# VoltageRegulators.net
KiCad netlist of a schematic drawn in Altium Designer
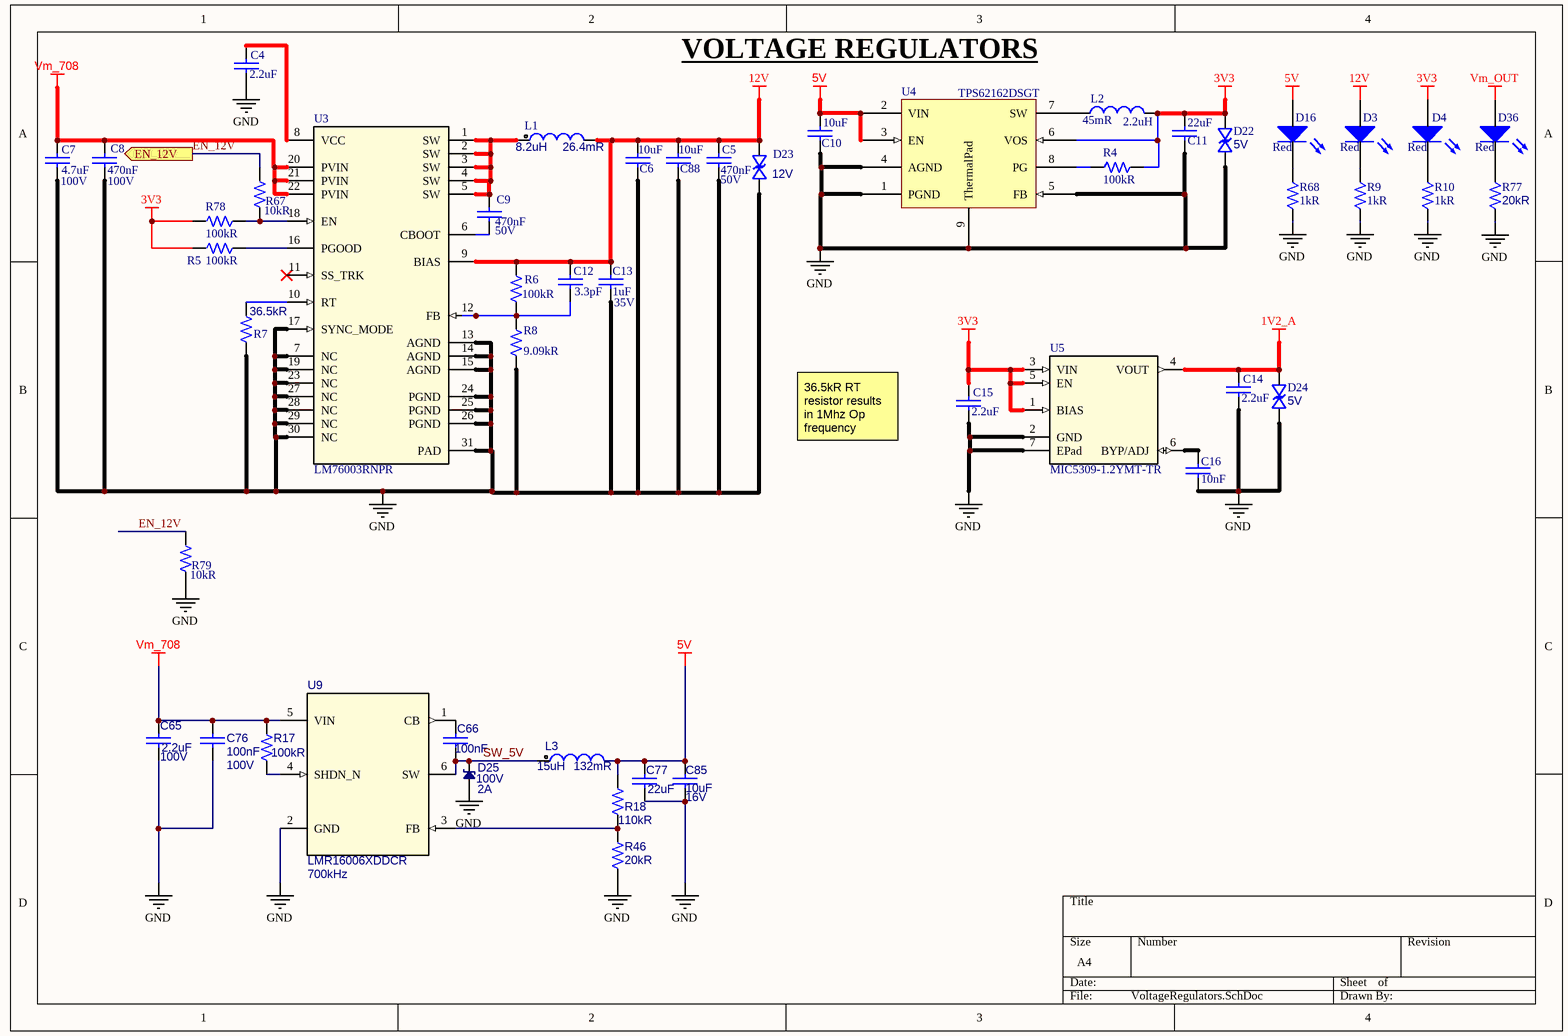
[diagram p0: VoltageRegulators.SchDoc]

(export (version "E")
  (design (tool "Eeschema 10.0.6"))
  (components
    (comp (ref "C4")
      (value "Capacitor")
      (footprint "CAP0402")
      (fields (field (name "CAPACITANCE") "2.2uF"))
      (libsource (lib "BPL-ShematicLibrary") (part "Capacitor"))
    )
    (comp (ref "C5")
      (value "Capacitor")
      (footprint "CAP0603")
      (fields (field (name "CAPACITANCE") "470nF") (field (name "VOLTAGE RATING") "50V"))
      (libsource (lib "") (part "Capacitor_1"))
    )
    (comp (ref "C6")
      (value "10uF")
      (footprint "CAP0603")
      (description "Capacitor")
      (fields
        (field (name "MANUFACTURER") "Murata")
        (field (name "MANUFACTURER PART NUMBER") "GRM188R61E106MA73J")
      )
      (libsource (lib "") (part "Capacitor_1"))
    )
    (comp (ref "C7")
      (value "Capacitor")
      (footprint "CAP1210")
      (fields
        (field (name "CAPACITANCE") "4.7uF")
        (field (name "VOLTAGE RATING") "100V")
        (field (name "TOLERANCE") "10%")
      )
      (libsource (lib "") (part "Capacitor_1"))
    )
    (comp (ref "C8")
      (value "Capacitor")
      (footprint "CAP0805")
      (fields (field (name "CAPACITANCE") "470nF") (field (name "VOLTAGE RATING") "100V"))
      (libsource (lib "") (part "Capacitor_1"))
    )
    (comp (ref "C9")
      (value "Capacitor")
      (footprint "CAP0603")
      (fields (field (name "CAPACITANCE") "470nF") (field (name "VOLTAGE RATING") "50V"))
      (libsource (lib "") (part "Capacitor_1"))
    )
    (comp (ref "C10")
      (value "10uF")
      (footprint "CAP0603")
      (description "Capacitor")
      (fields
        (field (name "MANUFACTURER") "Murata")
        (field (name "MANUFACTURER PART NUMBER") "GRM188R61E106MA73J")
      )
      (libsource (lib "") (part "Capacitor_1"))
    )
    (comp (ref "C11")
      (value "22uF")
      (footprint "CAP0603")
      (description "Capacitor")
      (fields
        (field (name "MANUFACTURER") "Samsung")
        (field (name "MANUFACTURER PART NUMBER") "CL10A226MO7JZNC")
      )
      (libsource (lib "") (part "Capacitor_1"))
    )
    (comp (ref "C12")
      (value "Capacitor")
      (footprint "CAP0402")
      (fields (field (name "CAPACITANCE") "3.3pF"))
      (libsource (lib "BPL-ShematicLibrary") (part "Capacitor"))
    )
    (comp (ref "C13")
      (value "Capacitor")
      (footprint "CAP0402")
      (fields (field (name "VOLTAGE RATING") "35V") (field (name "CAPACITANCE") "1uF"))
      (libsource (lib "") (part "Capacitor_1"))
    )
    (comp (ref "C14")
      (value "Capacitor")
      (footprint "CAP0402")
      (fields (field (name "CAPACITANCE") "2.2uF"))
      (libsource (lib "BPL-ShematicLibrary") (part "Capacitor"))
    )
    (comp (ref "C15")
      (value "Capacitor")
      (footprint "CAP0402")
      (fields (field (name "CAPACITANCE") "2.2uF"))
      (libsource (lib "BPL-ShematicLibrary") (part "Capacitor"))
    )
    (comp (ref "C16")
      (value "Capacitor")
      (footprint "CAP0402")
      (fields (field (name "CAPACITANCE") "10nF"))
      (libsource (lib "BPL-ShematicLibrary") (part "Capacitor"))
    )
    (comp (ref "C65")
      (value "Capacitor")
      (footprint "CAP1206")
      (description "CAP CER 2.2UF 100V X7R 1206")
      (fields (field (name "CAPACITANCE") "2.2uF") (field (name "VOLTAGE RATING") "100V"))
      (libsource (lib "BPL-ShematicLibrary") (part "Capacitor"))
    )
    (comp (ref "C66")
      (value "Capacitor")
      (footprint "CAP0402")
      (fields
        (field (name "MANUFACTURER") "TDK")
        (field (name "MANUFACTURER PART NUMBER") "CGA2B3X7R1H104K050BB")
        (field (name "CAPACITANCE") "100nF")
        (field (name "TOLERANCE") "10%")
      )
      (libsource (lib "") (part "Capacitor_1"))
    )
    (comp (ref "C76")
      (value "Capacitor")
      (footprint "CAP0402")
      (description "0402 0.1 uF 100 V ±10% Tolerance X5R SMT Multilayer Ceramic Capacitor")
      (fields (field (name "CAPACITANCE") "100nF") (field (name "VOLTAGE RATING") "100V"))
      (libsource (lib "BPL-ShematicLibrary") (part "Capacitor"))
    )
    (comp (ref "C77")
      (value "Capacitor")
      (footprint "CAP0805")
      (description "CAP CER 22UF 16V X5R 0805")
      (fields (field (name "CAPACITANCE") "22uF"))
      (libsource (lib "BPL-ShematicLibrary") (part "Capacitor"))
    )
    (comp (ref "C85")
      (value "Capacitor")
      (footprint "CAP0603")
      (fields (field (name "CAPACITANCE") "10uF") (field (name "VOLTAGE RATING (DC)") "16V"))
      (libsource (lib "BPL-ShematicLibrary") (part "Capacitor"))
    )
    (comp (ref "C88")
      (value "10uF")
      (footprint "CAP0603")
      (description "Capacitor")
      (fields
        (field (name "MANUFACTURER") "Murata")
        (field (name "MANUFACTURER PART NUMBER") "GRM188R61E106MA73J")
      )
      (libsource (lib "") (part "Capacitor_1"))
    )
    (comp (ref "D3")
      (value "LED")
      (footprint "LED-0603-RED")
      (fields
        (field (name "MANUFACTURER") "Wurth Electronics Inc.")
        (field (name "MANUFACTURER PART NUMBER") "150060RS75000")
        (field (name "COLOUR") "Red")
      )
      (libsource (lib "BPL-ShematicLibrary") (part "LED"))
    )
    (comp (ref "D4")
      (value "LED")
      (footprint "LED-0603-RED")
      (fields
        (field (name "MANUFACTURER") "Wurth Electronics Inc.")
        (field (name "MANUFACTURER PART NUMBER") "150060RS75000")
        (field (name "COLOUR") "Red")
      )
      (libsource (lib "BPL-ShematicLibrary") (part "LED"))
    )
    (comp (ref "D16")
      (value "LED")
      (footprint "LED-0603-RED")
      (fields
        (field (name "MANUFACTURER") "Wurth Electronics Inc.")
        (field (name "MANUFACTURER PART NUMBER") "150060RS75000")
        (field (name "COLOUR") "Red")
      )
      (libsource (lib "BPL-ShematicLibrary") (part "LED"))
    )
    (comp (ref "D22")
      (value "TVS-Bidirectional")
      (footprint "SLP1006P2T")
      (description "TVS DIODE 5V 20V SLP1006P2T")
      (fields (field (name "REVERSE STANDOFF VOLTAGE") "5V"))
      (libsource (lib "BPL-ShematicLibrary") (part "TVS-Bidirectional"))
    )
    (comp (ref "D23")
      (value "TVS-Bidirectional")
      (footprint "SLP1006P2T")
      (description "TVS DIODE 12V 27V SLP1006P2T")
      (fields (field (name "WORKING VOLTAGE") "12V"))
      (libsource (lib "") (part "TVS-Bidirectional_1"))
    )
    (comp (ref "D24")
      (value "TVS-Bidirectional")
      (footprint "SLP1006P2T")
      (description "TVS DIODE 5V 20V SLP1006P2T")
      (fields (field (name "REVERSE STANDOFF VOLTAGE") "5V"))
      (libsource (lib "BPL-ShematicLibrary") (part "TVS-Bidirectional"))
    )
    (comp (ref "D25")
      (value "Diode")
      (footprint "SOD-123F")
      (description "DIODE SCHOTTKY 100V 2A SOD123F")
      (fields
        (field (name "MAX REVERSE VOLTAGE (DC)") "100V")
        (field (name "AVERAGE RECTIFIED CURRENT") "2A")
      )
      (libsource (lib "BPL-ShematicLibrary") (part "Diode_Shottky_2"))
    )
    (comp (ref "D36")
      (value "LED")
      (footprint "LED-0603-RED")
      (fields
        (field (name "MANUFACTURER") "Wurth Electronics Inc.")
        (field (name "MANUFACTURER PART NUMBER") "150060RS75000")
        (field (name "COLOUR") "Red")
      )
      (libsource (lib "BPL-ShematicLibrary") (part "LED"))
    )
    (comp (ref "L1")
      (value "Inductor")
      (footprint "IND_ XAL6060-682MEB")
      (fields
        (field (name "TOLERANCE") "20%")
        (field (name "INDUCTANCE") "8.2uH")
        (field (name "DC RESISTANCE (DCR)") "26.4mR")
      )
      (libsource (lib "BPL-ShematicLibrary") (part "Inductor"))
    )
    (comp (ref "L2")
      (value "Inductor")
      (footprint "IFSC-1515AH-ER2R2M01")
      (fields
        (field (name "TOLERANCE") "20%")
        (field (name "INDUCTANCE") "2.2uH")
        (field (name "DC RESISTANCE (DCR)") "45mR")
      )
      (libsource (lib "") (part "Inductor_1"))
    )
    (comp (ref "L3")
      (value "Inductor")
      (footprint "IND_74404043---A")
      (description "FIXED IND 15UH 1.45A 132 MOHM")
      (fields
        (field (name "INDUCTANCE") "15uH")
        (field (name "TOLERANCE") "20%")
        (field (name "DC RESISTANCE (DCR)") "132mR")
      )
      (libsource (lib "BPL-ShematicLibrary") (part "Inductor"))
    )
    (comp (ref "R4")
      (value "Resistor")
      (footprint "RES0402")
      (fields (field (name "TOLERANCE") "1%") (field (name "RESISTANCE") "100kR"))
      (libsource (lib "BPL-ShematicLibrary") (part "Resistor"))
    )
    (comp (ref "R5")
      (value "Resistor")
      (footprint "RES0402")
      (fields (field (name "TOLERANCE") "1%") (field (name "RESISTANCE") "100kR"))
      (libsource (lib "BPL-ShematicLibrary") (part "Resistor"))
    )
    (comp (ref "R6")
      (value "Resistor")
      (footprint "RES0402")
      (fields (field (name "TOLERANCE") "1%") (field (name "RESISTANCE") "100kR"))
      (libsource (lib "BPL-ShematicLibrary") (part "Resistor"))
    )
    (comp (ref "R7")
      (value "Resistor")
      (footprint "RES0402")
      (description "RES SMD 36.5KOHM 0.1% 1/16W 0402")
      (fields (field (name "RESISTANCE") "36.5kR") (field (name "TOLERANCE") "0.1%"))
      (libsource (lib "BPL-ShematicLibrary") (part "Resistor"))
    )
    (comp (ref "R8")
      (value "Resistor")
      (footprint "RES0402")
      (fields (field (name "TOLERANCE") "1%") (field (name "RESISTANCE") "9.09kR"))
      (libsource (lib "BPL-ShematicLibrary") (part "Resistor"))
    )
    (comp (ref "R9")
      (value "Resistor")
      (footprint "RES0402")
      (fields (field (name "TOLERANCE") "5%") (field (name "RESISTANCE") "1kR"))
      (libsource (lib "BPL-ShematicLibrary") (part "Resistor"))
    )
    (comp (ref "R10")
      (value "Resistor")
      (footprint "RES0402")
      (fields (field (name "TOLERANCE") "5%") (field (name "RESISTANCE") "1kR"))
      (libsource (lib "BPL-ShematicLibrary") (part "Resistor"))
    )
    (comp (ref "R17")
      (value "Resistor")
      (footprint "RES0402")
      (fields (field (name "TOLERANCE") "1%") (field (name "RESISTANCE") "100kR"))
      (libsource (lib "BPL-ShematicLibrary") (part "Resistor"))
    )
    (comp (ref "R18")
      (value "Resistor")
      (footprint "RES0402")
      (description "Res Thick Film 0402 110K Ohm 1% 0.063W(1/16W) ±100ppm/C Pad SMD Automotive T/R")
      (fields (field (name "RESISTANCE") "110kR") (field (name "TOLERANCE") "1%"))
      (libsource (lib "BPL-ShematicLibrary") (part "Resistor"))
    )
    (comp (ref "R46")
      (value "Resistor")
      (footprint "RES0402")
      (description "YAGEO - RC0402FR-0720KL - RES, THICK FILM, 20K, 1%, 0.0625W, 0402")
      (fields (field (name "TOLERANCE") "1%") (field (name "RESISTANCE") "20kR"))
      (libsource (lib "BPL-ShematicLibrary") (part "Resistor"))
    )
    (comp (ref "R67")
      (value "Resistor")
      (footprint "RES0402")
      (fields (field (name "RESISTANCE") "10kR") (field (name "TOLERANCE") "1%"))
      (libsource (lib "BPL-ShematicLibrary") (part "Resistor"))
    )
    (comp (ref "R68")
      (value "Resistor")
      (footprint "RES0402")
      (fields (field (name "TOLERANCE") "5%") (field (name "RESISTANCE") "1kR"))
      (libsource (lib "BPL-ShematicLibrary") (part "Resistor"))
    )
    (comp (ref "R77")
      (value "Resistor")
      (footprint "RES0603")
      (description "RES SMD 20K OHM 5% 1/4W 0603")
      (fields (field (name "TOLERANCE") "5%") (field (name "RESISTANCE") "20kR"))
      (libsource (lib "BPL-ShematicLibrary") (part "Resistor"))
    )
    (comp (ref "R78")
      (value "Resistor")
      (footprint "RES0402")
      (fields (field (name "TOLERANCE") "1%") (field (name "RESISTANCE") "100kR"))
      (libsource (lib "BPL-ShematicLibrary") (part "Resistor"))
    )
    (comp (ref "R79")
      (value "Resistor")
      (footprint "RES0402")
      (fields (field (name "RESISTANCE") "10kR") (field (name "TOLERANCE") "1%"))
      (libsource (lib "BPL-ShematicLibrary") (part "Resistor"))
    )
    (comp (ref "U3")
      (value "LM76003RNPR")
      (footprint "LM76003")
      (description "Buck Switching Regulator IC Positive Adjustable 1V 1 Output 3.5A 30-WFQFN Exposed Pad")
      (libsource (lib "BPL-ShematicLibrary") (part "LM76003RNPR"))
    )
    (comp (ref "U4")
      (value "3-17v Switching Reg")
      (footprint "TPS6216X")
      (fields (field (name "MANUFACTURER PART NUMBER 1") "TPS62162DSGT"))
      (libsource (lib "BPL-ShematicLibrary") (part "TPS6216X"))
    )
    (comp (ref "U5")
      (value "MIC5309-xx")
      (footprint "MIC5309")
      (description "Linear Voltage Regulator")
      (fields (field (name "MANUFACTURER PART NUMBER 1") "MIC5309-1.2YMT-TR"))
      (libsource (lib "BPL-ShematicLibrary") (part "MIC5309-xx"))
    )
    (comp (ref "U9")
      (value "IC REG BUCK ADJ 600MA TSOT23-6")
      (footprint "SOT23-6")
      (description "SIMPLE SWITCHER® 4V to 60V, 600mA Step-Down Regulator with Low Iq 6-SOT-23-THIN -40 to 125")
      (fields
        (field (name "MANUFACTURER PART NUMBER 1") "LMR16006XDDCR")
        (field (name "SWITCHING FREQUENCY") "700kHz")
      )
      (libsource (lib "BPL-ShematicLibrary") (part "LMR16006"))
    )
  )
  (nets
    (net (code "1") (name "/EN_12V") (class "Default")
      (node (ref "R67") (pin "2") (pinfunction "2_2") (pintype "passive"))
      (node (ref "R79") (pin "2") (pinfunction "2_2") (pintype "passive"))
    )
    (net (code "2") (name "/SW_5V") (class "Default")
      (node (ref "C66") (pin "2") (pinfunction "2_2") (pintype "passive"))
      (node (ref "D25") (pin "1") (pinfunction "1_1") (pintype "passive"))
      (node (ref "L3") (pin "1") (pinfunction "1_1") (pintype "passive"))
      (node (ref "U9") (pin "6") (pinfunction "SW_6") (pintype "power_in"))
    )
    (net (code "3") (name "1V2_A") (class "Default")
      (node (ref "C14") (pin "1") (pinfunction "1_1") (pintype "passive"))
      (node (ref "D24") (pin "1") (pinfunction "1_1") (pintype "passive"))
      (node (ref "U5") (pin "4") (pinfunction "VOUT_4") (pintype "output"))
    )
    (net (code "4") (name "3V3") (class "Default")
      (node (ref "C11") (pin "1") (pinfunction "1_1") (pintype "passive"))
      (node (ref "C15") (pin "1") (pinfunction "1_1") (pintype "passive"))
      (node (ref "D22") (pin "1") (pinfunction "1_1") (pintype "passive"))
      (node (ref "D4") (pin "2") (pinfunction "2_2") (pintype "passive"))
      (node (ref "L2") (pin "2") (pinfunction "2_2") (pintype "passive"))
      (node (ref "R4") (pin "1") (pinfunction "1_1") (pintype "passive"))
      (node (ref "R5") (pin "2") (pinfunction "2_2") (pintype "passive"))
      (node (ref "R78") (pin "2") (pinfunction "2_2") (pintype "passive"))
      (node (ref "U4") (pin "6") (pinfunction "VOS_6") (pintype "input"))
      (node (ref "U5") (pin "1") (pinfunction "BIAS_1") (pintype "input"))
      (node (ref "U5") (pin "3") (pinfunction "VIN_3") (pintype "input"))
      (node (ref "U5") (pin "5") (pinfunction "EN_5") (pintype "input"))
    )
    (net (code "5") (name "5V") (class "Default")
      (node (ref "C10") (pin "1") (pinfunction "1_1") (pintype "passive"))
      (node (ref "C77") (pin "1") (pinfunction "1_1") (pintype "passive"))
      (node (ref "C85") (pin "1") (pinfunction "1_1") (pintype "passive"))
      (node (ref "D16") (pin "2") (pinfunction "2_2") (pintype "passive"))
      (node (ref "L3") (pin "2") (pinfunction "2_2") (pintype "passive"))
      (node (ref "R18") (pin "2") (pinfunction "2_2") (pintype "passive"))
      (node (ref "U4") (pin "2") (pinfunction "VIN_2") (pintype "power_in"))
      (node (ref "U4") (pin "3") (pinfunction "EN_3") (pintype "input"))
    )
    (net (code "6") (name "12V") (class "Default")
      (node (ref "C12") (pin "1") (pinfunction "1_1") (pintype "passive"))
      (node (ref "C13") (pin "2") (pinfunction "2_2") (pintype "passive"))
      (node (ref "C5") (pin "1") (pinfunction "1_1") (pintype "passive"))
      (node (ref "C6") (pin "1") (pinfunction "1_1") (pintype "passive"))
      (node (ref "C88") (pin "1") (pinfunction "1_1") (pintype "passive"))
      (node (ref "D23") (pin "2") (pinfunction "2_2") (pintype "passive"))
      (node (ref "D3") (pin "2") (pinfunction "2_2") (pintype "passive"))
      (node (ref "L1") (pin "2") (pinfunction "2_2") (pintype "passive"))
      (node (ref "R6") (pin "2") (pinfunction "2_2") (pintype "passive"))
      (node (ref "U3") (pin "9") (pinfunction "BIAS_9") (pintype "passive"))
    )
    (net (code "7") (name "GND") (class "Default")
      (node (ref "C10") (pin "2") (pinfunction "2_2") (pintype "passive"))
      (node (ref "C11") (pin "2") (pinfunction "2_2") (pintype "passive"))
      (node (ref "C13") (pin "1") (pinfunction "1_1") (pintype "passive"))
      (node (ref "C14") (pin "2") (pinfunction "2_2") (pintype "passive"))
      (node (ref "C15") (pin "2") (pinfunction "2_2") (pintype "passive"))
      (node (ref "C16") (pin "2") (pinfunction "2_2") (pintype "passive"))
      (node (ref "C4") (pin "2") (pinfunction "2_2") (pintype "passive"))
      (node (ref "C5") (pin "2") (pinfunction "2_2") (pintype "passive"))
      (node (ref "C6") (pin "2") (pinfunction "2_2") (pintype "passive"))
      (node (ref "C65") (pin "2") (pinfunction "2_2") (pintype "passive"))
      (node (ref "C7") (pin "1") (pinfunction "1_1") (pintype "passive"))
      (node (ref "C76") (pin "2") (pinfunction "2_2") (pintype "passive"))
      (node (ref "C77") (pin "2") (pinfunction "2_2") (pintype "passive"))
      (node (ref "C8") (pin "2") (pinfunction "2_2") (pintype "passive"))
      (node (ref "C85") (pin "2") (pinfunction "2_2") (pintype "passive"))
      (node (ref "C88") (pin "2") (pinfunction "2_2") (pintype "passive"))
      (node (ref "D22") (pin "2") (pinfunction "2_2") (pintype "passive"))
      (node (ref "D23") (pin "1") (pinfunction "1_1") (pintype "passive"))
      (node (ref "D24") (pin "2") (pinfunction "2_2") (pintype "passive"))
      (node (ref "D25") (pin "2") (pinfunction "2_2") (pintype "passive"))
      (node (ref "R10") (pin "1") (pinfunction "1_1") (pintype "passive"))
      (node (ref "R46") (pin "1") (pinfunction "1_1") (pintype "passive"))
      (node (ref "R68") (pin "1") (pinfunction "1_1") (pintype "passive"))
      (node (ref "R7") (pin "1") (pinfunction "1_1") (pintype "passive"))
      (node (ref "R77") (pin "1") (pinfunction "1_1") (pintype "passive"))
      (node (ref "R79") (pin "1") (pinfunction "1_1") (pintype "passive"))
      (node (ref "R8") (pin "1") (pinfunction "1_1") (pintype "passive"))
      (node (ref "R9") (pin "1") (pinfunction "1_1") (pintype "passive"))
      (node (ref "U3") (pin "13") (pinfunction "AGND_13") (pintype "power_in"))
      (node (ref "U3") (pin "14") (pinfunction "AGND_14") (pintype "power_in"))
      (node (ref "U3") (pin "15") (pinfunction "AGND_15") (pintype "power_in"))
      (node (ref "U3") (pin "17") (pinfunction "SYNC_MODE_17") (pintype "input"))
      (node (ref "U3") (pin "19") (pinfunction "NC_19") (pintype "passive"))
      (node (ref "U3") (pin "23") (pinfunction "NC_23") (pintype "passive"))
      (node (ref "U3") (pin "24") (pinfunction "PGND_24") (pintype "power_in"))
      (node (ref "U3") (pin "25") (pinfunction "PGND_25") (pintype "power_in"))
      (node (ref "U3") (pin "26") (pinfunction "PGND_26") (pintype "power_in"))
      (node (ref "U3") (pin "27") (pinfunction "NC_27") (pintype "passive"))
      (node (ref "U3") (pin "28") (pinfunction "NC_28") (pintype "passive"))
      (node (ref "U3") (pin "29") (pinfunction "NC_29") (pintype "passive"))
      (node (ref "U3") (pin "30") (pinfunction "NC_30") (pintype "passive"))
      (node (ref "U3") (pin "31") (pinfunction "PAD_31") (pintype "power_in"))
      (node (ref "U3") (pin "7") (pinfunction "NC_7") (pintype "passive"))
      (node (ref "U4") (pin "1") (pinfunction "PGND_1") (pintype "power_in"))
      (node (ref "U4") (pin "4") (pinfunction "AGND_4") (pintype "power_in"))
      (node (ref "U4") (pin "5") (pinfunction "FB_5") (pintype "input"))
      (node (ref "U4") (pin "9") (pinfunction "ThermalPad_9") (pintype "power_in"))
      (node (ref "U5") (pin "2") (pinfunction "GND_2") (pintype "power_in"))
      (node (ref "U5") (pin "7") (pinfunction "EPad_7") (pintype "passive"))
      (node (ref "U9") (pin "2") (pinfunction "GND_2") (pintype "power_in"))
    )
    (net (code "8") (name "Net-(C9-Pad1)") (class "Default")
      (node (ref "C9") (pin "1") (pinfunction "1_1") (pintype "passive"))
      (node (ref "L1") (pin "1") (pinfunction "1_1") (pintype "passive"))
      (node (ref "U3") (pin "1") (pinfunction "SW_1") (pintype "power_in"))
      (node (ref "U3") (pin "2") (pinfunction "SW_2") (pintype "power_in"))
      (node (ref "U3") (pin "3") (pinfunction "SW_3") (pintype "power_in"))
      (node (ref "U3") (pin "4") (pinfunction "SW_4") (pintype "power_in"))
      (node (ref "U3") (pin "5") (pinfunction "SW_5") (pintype "power_in"))
    )
    (net (code "9") (name "Net-(D3-Pad1)") (class "Default")
      (node (ref "D3") (pin "1") (pinfunction "1_1") (pintype "passive"))
      (node (ref "R9") (pin "2") (pinfunction "2_2") (pintype "passive"))
    )
    (net (code "10") (name "Net-(D4-Pad1)") (class "Default")
      (node (ref "D4") (pin "1") (pinfunction "1_1") (pintype "passive"))
      (node (ref "R10") (pin "2") (pinfunction "2_2") (pintype "passive"))
    )
    (net (code "11") (name "Net-(D16-Pad1)") (class "Default")
      (node (ref "D16") (pin "1") (pinfunction "1_1") (pintype "passive"))
      (node (ref "R68") (pin "2") (pinfunction "2_2") (pintype "passive"))
    )
    (net (code "12") (name "Net-(D36-Pad1)") (class "Default")
      (node (ref "D36") (pin "1") (pinfunction "1_1") (pintype "passive"))
      (node (ref "R77") (pin "2") (pinfunction "2_2") (pintype "passive"))
    )
    (net (code "13") (name "Net-(U3-CBOOT)") (class "Default")
      (node (ref "C9") (pin "2") (pinfunction "2_2") (pintype "passive"))
      (node (ref "U3") (pin "6") (pinfunction "CBOOT_6") (pintype "power_in"))
    )
    (net (code "14") (name "Net-(U3-EN)") (class "Default")
      (node (ref "R67") (pin "1") (pinfunction "1_1") (pintype "passive"))
      (node (ref "R78") (pin "1") (pinfunction "1_1") (pintype "passive"))
      (node (ref "U3") (pin "18") (pinfunction "EN_18") (pintype "input"))
    )
    (net (code "15") (name "Net-(U3-FB)") (class "Default")
      (node (ref "C12") (pin "2") (pinfunction "2_2") (pintype "passive"))
      (node (ref "R6") (pin "1") (pinfunction "1_1") (pintype "passive"))
      (node (ref "R8") (pin "2") (pinfunction "2_2") (pintype "passive"))
      (node (ref "U3") (pin "12") (pinfunction "FB_12") (pintype "input"))
    )
    (net (code "16") (name "Net-(U3-PGOOD)") (class "Default")
      (node (ref "R5") (pin "1") (pinfunction "1_1") (pintype "passive"))
      (node (ref "U3") (pin "16") (pinfunction "PGOOD_16") (pintype "open_collector"))
    )
    (net (code "17") (name "Net-(U3-RT)") (class "Default")
      (node (ref "R7") (pin "2") (pinfunction "2_2") (pintype "passive"))
      (node (ref "U3") (pin "10") (pinfunction "RT_10") (pintype "input"))
    )
    (net (code "18") (name "Net-(U3-VCC)") (class "Default")
      (node (ref "C4") (pin "1") (pinfunction "1_1") (pintype "passive"))
      (node (ref "U3") (pin "8") (pinfunction "VCC_8") (pintype "power_in"))
    )
    (net (code "19") (name "Net-(U4-PG)") (class "Default")
      (node (ref "R4") (pin "2") (pinfunction "2_2") (pintype "passive"))
      (node (ref "U4") (pin "8") (pinfunction "PG_8") (pintype "power_in"))
    )
    (net (code "20") (name "Net-(U4-SW)") (class "Default")
      (node (ref "L2") (pin "1") (pinfunction "1_1") (pintype "passive"))
      (node (ref "U4") (pin "7") (pinfunction "SW_7") (pintype "power_in"))
    )
    (net (code "21") (name "Net-(U5-BYP{slash}ADJ)") (class "Default")
      (node (ref "C16") (pin "1") (pinfunction "1_1") (pintype "passive"))
      (node (ref "U5") (pin "6") (pinfunction "BYP/ADJ_6") (pintype "bidirectional"))
    )
    (net (code "22") (name "Net-(U9-CB)") (class "Default")
      (node (ref "C66") (pin "1") (pinfunction "1_1") (pintype "passive"))
      (node (ref "U9") (pin "1") (pinfunction "CB_1") (pintype "output"))
    )
    (net (code "23") (name "Net-(U9-FB)") (class "Default")
      (node (ref "R18") (pin "1") (pinfunction "1_1") (pintype "passive"))
      (node (ref "R46") (pin "2") (pinfunction "2_2") (pintype "passive"))
      (node (ref "U9") (pin "3") (pinfunction "FB_3") (pintype "input"))
    )
    (net (code "24") (name "Net-(U9-SHDN_N)") (class "Default")
      (node (ref "R17") (pin "1") (pinfunction "1_1") (pintype "passive"))
      (node (ref "U9") (pin "4") (pinfunction "SHDN_N_4") (pintype "input"))
    )
    (net (code "25") (name "Vm_708") (class "Default")
      (node (ref "C65") (pin "1") (pinfunction "1_1") (pintype "passive"))
      (node (ref "C7") (pin "2") (pinfunction "2_2") (pintype "passive"))
      (node (ref "C76") (pin "1") (pinfunction "1_1") (pintype "passive"))
      (node (ref "C8") (pin "1") (pinfunction "1_1") (pintype "passive"))
      (node (ref "R17") (pin "2") (pinfunction "2_2") (pintype "passive"))
      (node (ref "U3") (pin "20") (pinfunction "PVIN_20") (pintype "power_in"))
      (node (ref "U3") (pin "21") (pinfunction "PVIN_21") (pintype "power_in"))
      (node (ref "U3") (pin "22") (pinfunction "PVIN_22") (pintype "power_in"))
      (node (ref "U9") (pin "5") (pinfunction "VIN_5") (pintype "power_in"))
    )
    (net (code "26") (name "Vm_OUT") (class "Default")
      (node (ref "D36") (pin "2") (pinfunction "2_2") (pintype "passive"))
    )
    (net (code "27") (name "unconnected-(U3-SS_TRK-Pad11)") (class "Default")
      (node (ref "U3") (pin "11") (pinfunction "SS_TRK_11") (pintype "input+no_connect"))
    )
  )
)
